# SCH_pcb-try-1_2025-03-21.net
KiCad netlist of a schematic drawn in EasyEDA
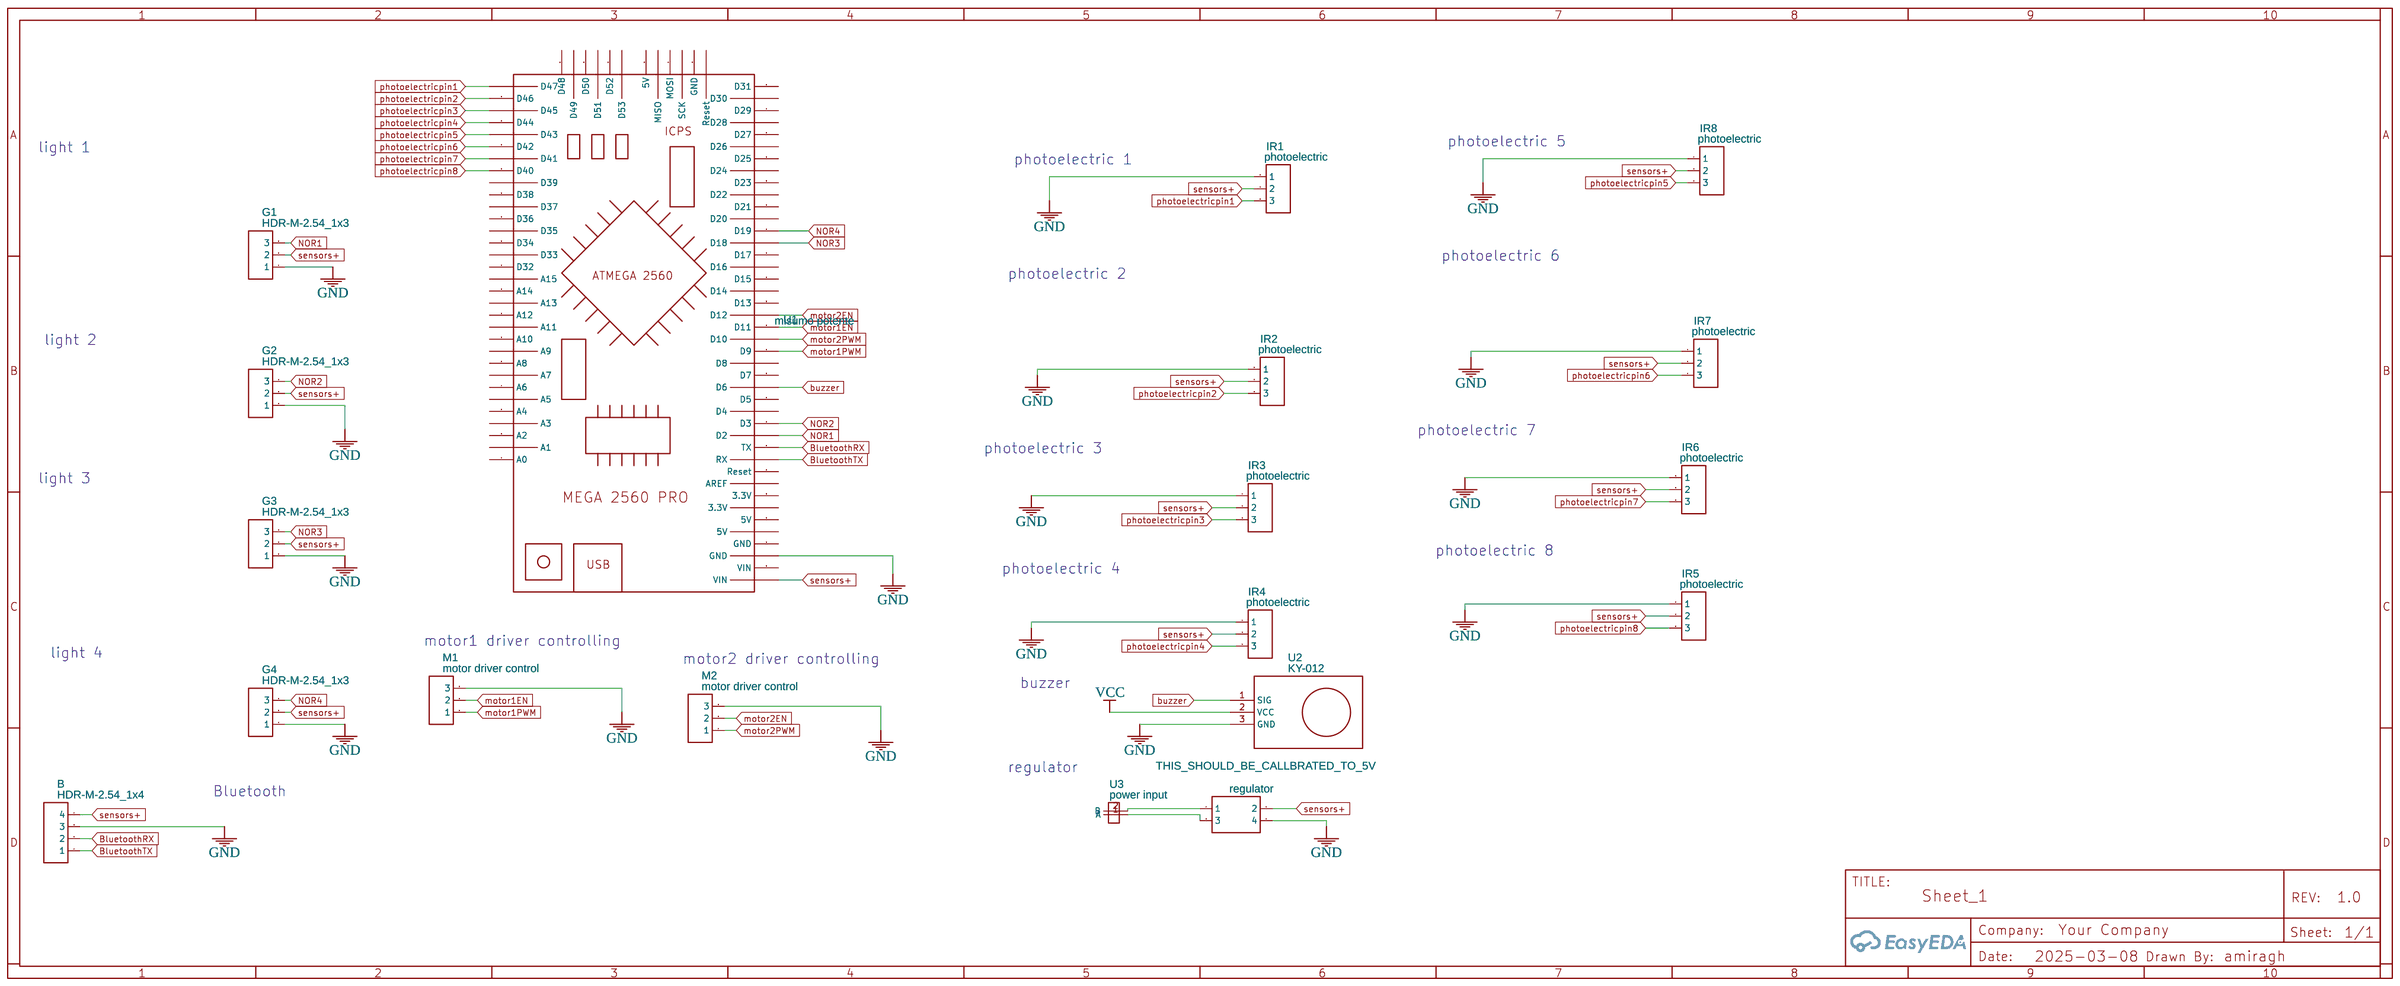
[diagram p0: schematic sheet]

(export (version "E")
  (design (tool "Eeschema 10.0.6"))
  (components
    (comp (ref "B") (value "HDR-M-2.54_1x4") (libsource (lib "") (part "HDR-M-2.54_1x4")))
    (comp (ref "G1") (value "HDR-M-2.54_1x3") (libsource (lib "") (part "HDR-M-2.54_1x3_1")))
    (comp (ref "G2") (value "HDR-M-2.54_1x3") (libsource (lib "") (part "HDR-M-2.54_1x3_1")))
    (comp (ref "G3") (value "HDR-M-2.54_1x3") (libsource (lib "") (part "HDR-M-2.54_1x3_1")))
    (comp (ref "G4") (value "HDR-M-2.54_1x3") (libsource (lib "") (part "HDR-M-2.54_1x3_1")))
    (comp (ref "IR1") (value "photoelectric") (libsource (lib "") (part "HDR-M-2.54_1x3")))
    (comp (ref "IR2") (value "photoelectric") (libsource (lib "") (part "HDR-M-2.54_1x3")))
    (comp (ref "IR3") (value "photoelectric") (libsource (lib "") (part "HDR-M-2.54_1x3")))
    (comp (ref "IR4") (value "photoelectric") (libsource (lib "") (part "HDR-M-2.54_1x3")))
    (comp (ref "IR5") (value "photoelectric") (libsource (lib "") (part "HDR-M-2.54_1x3")))
    (comp (ref "IR6") (value "photoelectric") (libsource (lib "") (part "HDR-M-2.54_1x3")))
    (comp (ref "IR7") (value "photoelectric") (libsource (lib "") (part "HDR-M-2.54_1x3")))
    (comp (ref "IR8") (value "photoelectric") (libsource (lib "") (part "HDR-M-2.54_1x3")))
    (comp (ref "M1") (value "motor driver control") (libsource (lib "") (part "HDR-M-2.54_1x3_2")))
    (comp (ref "M2") (value "motor driver control") (libsource (lib "") (part "HDR-M-2.54_1x3_2")))
    (comp (ref "THIS_SHOULD_BE_CALLBRATED_TO_5V")
      (value "regulator")
      (libsource (lib "") (part "HDR-M-2.54_2x2"))
    )
    (comp (ref "U1")
      (value "misumo potente")
      (fields (field (name "Manufacturer Part") "Arduino Mega 2560 Pro Mini"))
      (libsource (lib "") (part "misumo potente"))
    )
    (comp (ref "U2") (value "KY-012") (libsource (lib "") (part "KY-012")))
    (comp (ref "U3")
      (value "power input")
      (fields (field (name "Manufacturer Part") "1725656") (field (name "Manufacturer") "Phoenix Contact"))
      (libsource (lib "") (part "SCHLIB_2-Pin-Fixed-Terminal-Blocks-2.54-mm_2025-03-11"))
    )
  )
  (nets
    (net (code "1") (name "BluetoothRX") (class "Default")
      (node (ref "B") (pin "2") (pinfunction "2_2") (pintype "unspecified"))
      (node (ref "U1") (pin "75") (pinfunction "TX_75") (pintype "unspecified"))
    )
    (net (code "2") (name "BluetoothTX") (class "Default")
      (node (ref "B") (pin "1") (pinfunction "1_1") (pintype "unspecified"))
      (node (ref "U1") (pin "76") (pinfunction "RX_76") (pintype "unspecified"))
    )
    (net (code "3") (name "GND") (class "Default")
      (node (ref "B") (pin "3") (pinfunction "3_3") (pintype "unspecified"))
      (node (ref "G1") (pin "1") (pinfunction "1_1") (pintype "input"))
      (node (ref "G2") (pin "1") (pinfunction "1_1") (pintype "input"))
      (node (ref "G3") (pin "1") (pinfunction "1_1") (pintype "input"))
      (node (ref "G4") (pin "1") (pinfunction "1_1") (pintype "input"))
      (node (ref "IR1") (pin "1") (pinfunction "1_1") (pintype "input"))
      (node (ref "IR2") (pin "1") (pinfunction "1_1") (pintype "input"))
      (node (ref "IR3") (pin "1") (pinfunction "1_1") (pintype "input"))
      (node (ref "IR4") (pin "1") (pinfunction "1_1") (pintype "input"))
      (node (ref "IR5") (pin "1") (pinfunction "1_1") (pintype "input"))
      (node (ref "IR6") (pin "1") (pinfunction "1_1") (pintype "input"))
      (node (ref "IR7") (pin "1") (pinfunction "1_1") (pintype "input"))
      (node (ref "IR8") (pin "1") (pinfunction "1_1") (pintype "input"))
      (node (ref "M1") (pin "3") (pinfunction "3_3") (pintype "input"))
      (node (ref "M2") (pin "3") (pinfunction "3_3") (pintype "input"))
      (node (ref "THIS_SHOULD_BE_CALLBRATED_TO_5V") (pin "4") (pinfunction "4_4") (pintype "input"))
      (node (ref "U1") (pin "84") (pinfunction "GND_84") (pintype "unspecified"))
      (node (ref "U2") (pin "3") (pinfunction "GND_3") (pintype "unspecified"))
    )
    (net (code "4") (name "NOR1") (class "Default")
      (node (ref "G1") (pin "3") (pinfunction "3_3") (pintype "input"))
      (node (ref "U1") (pin "74") (pinfunction "D2_74") (pintype "unspecified"))
    )
    (net (code "5") (name "NOR2") (class "Default")
      (node (ref "G2") (pin "3") (pinfunction "3_3") (pintype "input"))
      (node (ref "U1") (pin "73") (pinfunction "D3_73") (pintype "unspecified"))
    )
    (net (code "6") (name "NOR3") (class "Default")
      (node (ref "G3") (pin "3") (pinfunction "3_3") (pintype "input"))
      (node (ref "U1") (pin "58") (pinfunction "D18_58") (pintype "unspecified"))
    )
    (net (code "7") (name "NOR4") (class "Default")
      (node (ref "G4") (pin "3") (pinfunction "3_3") (pintype "input"))
      (node (ref "U1") (pin "57") (pinfunction "D19_57") (pintype "unspecified"))
    )
    (net (code "8") (name "Net-(U3-A)") (class "Default")
      (node (ref "THIS_SHOULD_BE_CALLBRATED_TO_5V") (pin "3") (pinfunction "3_3") (pintype "input"))
      (node (ref "U3") (pin "1") (pinfunction "A_1") (pintype "unspecified"))
    )
    (net (code "9") (name "Net-(U3-B)") (class "Default")
      (node (ref "THIS_SHOULD_BE_CALLBRATED_TO_5V") (pin "1") (pinfunction "1_1") (pintype "input"))
      (node (ref "U3") (pin "2") (pinfunction "B_2") (pintype "unspecified"))
    )
    (net (code "10") (name "VCC") (class "Default")
      (node (ref "U2") (pin "2") (pinfunction "VCC_2") (pintype "unspecified"))
    )
    (net (code "11") (name "buzzer") (class "Default")
      (node (ref "U1") (pin "70") (pinfunction "D6_70") (pintype "unspecified"))
      (node (ref "U2") (pin "1") (pinfunction "SIG_1") (pintype "unspecified"))
    )
    (net (code "12") (name "motor1EN") (class "Default")
      (node (ref "M1") (pin "2") (pinfunction "2_2") (pintype "input"))
      (node (ref "U1") (pin "65") (pinfunction "D11_65") (pintype "unspecified"))
    )
    (net (code "13") (name "motor1PWM") (class "Default")
      (node (ref "M1") (pin "1") (pinfunction "1_1") (pintype "input"))
      (node (ref "U1") (pin "67") (pinfunction "D9_67") (pintype "unspecified"))
    )
    (net (code "14") (name "motor2EN") (class "Default")
      (node (ref "M2") (pin "2") (pinfunction "2_2") (pintype "input"))
      (node (ref "U1") (pin "64") (pinfunction "D12_64") (pintype "unspecified"))
    )
    (net (code "15") (name "motor2PWM") (class "Default")
      (node (ref "M2") (pin "1") (pinfunction "1_1") (pintype "input"))
      (node (ref "U1") (pin "66") (pinfunction "D10_66") (pintype "unspecified"))
    )
    (net (code "16") (name "photoelectricpin1") (class "Default")
      (node (ref "IR1") (pin "3") (pinfunction "3_3") (pintype "input"))
      (node (ref "U1") (pin "32") (pinfunction "D47_32") (pintype "unspecified"))
    )
    (net (code "17") (name "photoelectricpin2") (class "Default")
      (node (ref "IR2") (pin "3") (pinfunction "3_3") (pintype "input"))
      (node (ref "U1") (pin "31") (pinfunction "D46_31") (pintype "unspecified"))
    )
    (net (code "18") (name "photoelectricpin3") (class "Default")
      (node (ref "IR3") (pin "3") (pinfunction "3_3") (pintype "input"))
      (node (ref "U1") (pin "30") (pinfunction "D45_30") (pintype "unspecified"))
    )
    (net (code "19") (name "photoelectricpin4") (class "Default")
      (node (ref "IR4") (pin "3") (pinfunction "3_3") (pintype "input"))
      (node (ref "U1") (pin "29") (pinfunction "D44_29") (pintype "unspecified"))
    )
    (net (code "20") (name "photoelectricpin5") (class "Default")
      (node (ref "IR8") (pin "3") (pinfunction "3_3") (pintype "input"))
      (node (ref "U1") (pin "28") (pinfunction "D43_28") (pintype "unspecified"))
    )
    (net (code "21") (name "photoelectricpin6") (class "Default")
      (node (ref "IR7") (pin "3") (pinfunction "3_3") (pintype "input"))
      (node (ref "U1") (pin "27") (pinfunction "D42_27") (pintype "unspecified"))
    )
    (net (code "22") (name "photoelectricpin7") (class "Default")
      (node (ref "IR6") (pin "3") (pinfunction "3_3") (pintype "input"))
      (node (ref "U1") (pin "26") (pinfunction "D41_26") (pintype "unspecified"))
    )
    (net (code "23") (name "photoelectricpin8") (class "Default")
      (node (ref "IR5") (pin "3") (pinfunction "3_3") (pintype "input"))
      (node (ref "U1") (pin "25") (pinfunction "D40_25") (pintype "unspecified"))
    )
    (net (code "24") (name "sensors+") (class "Default")
      (node (ref "B") (pin "4") (pinfunction "4_4") (pintype "unspecified"))
      (node (ref "G1") (pin "2") (pinfunction "2_2") (pintype "input"))
      (node (ref "G2") (pin "2") (pinfunction "2_2") (pintype "input"))
      (node (ref "G3") (pin "2") (pinfunction "2_2") (pintype "input"))
      (node (ref "G4") (pin "2") (pinfunction "2_2") (pintype "input"))
      (node (ref "IR1") (pin "2") (pinfunction "2_2") (pintype "input"))
      (node (ref "IR2") (pin "2") (pinfunction "2_2") (pintype "input"))
      (node (ref "IR3") (pin "2") (pinfunction "2_2") (pintype "input"))
      (node (ref "IR4") (pin "2") (pinfunction "2_2") (pintype "input"))
      (node (ref "IR5") (pin "2") (pinfunction "2_2") (pintype "input"))
      (node (ref "IR6") (pin "2") (pinfunction "2_2") (pintype "input"))
      (node (ref "IR7") (pin "2") (pinfunction "2_2") (pintype "input"))
      (node (ref "IR8") (pin "2") (pinfunction "2_2") (pintype "input"))
      (node (ref "THIS_SHOULD_BE_CALLBRATED_TO_5V") (pin "2") (pinfunction "2_2") (pintype "input"))
      (node (ref "U1") (pin "86") (pinfunction "VIN_86") (pintype "unspecified"))
    )
    (net (code "25") (name "unconnected-(U1-3.3V-Pad79)") (class "Default")
      (node (ref "U1") (pin "79") (pinfunction "3.3V_79") (pintype "unspecified"))
    )
    (net (code "26") (name "unconnected-(U1-3.3V-Pad80)") (class "Default")
      (node (ref "U1") (pin "80") (pinfunction "3.3V_80") (pintype "unspecified"))
    )
    (net (code "27") (name "unconnected-(U1-5V-Pad39)") (class "Default")
      (node (ref "U1") (pin "39") (pinfunction "5V_39") (pintype "unspecified"))
    )
    (net (code "28") (name "unconnected-(U1-5V-Pad81)") (class "Default")
      (node (ref "U1") (pin "81") (pinfunction "5V_81") (pintype "unspecified"))
    )
    (net (code "29") (name "unconnected-(U1-5V-Pad82)") (class "Default")
      (node (ref "U1") (pin "82") (pinfunction "5V_82") (pintype "unspecified"))
    )
    (net (code "30") (name "unconnected-(U1-A0-Pad1)") (class "Default")
      (node (ref "U1") (pin "1") (pinfunction "A0_1") (pintype "unspecified"))
    )
    (net (code "31") (name "unconnected-(U1-A1-Pad2)") (class "Default")
      (node (ref "U1") (pin "2") (pinfunction "A1_2") (pintype "unspecified"))
    )
    (net (code "32") (name "unconnected-(U1-A2-Pad3)") (class "Default")
      (node (ref "U1") (pin "3") (pinfunction "A2_3") (pintype "unspecified"))
    )
    (net (code "33") (name "unconnected-(U1-A3-Pad4)") (class "Default")
      (node (ref "U1") (pin "4") (pinfunction "A3_4") (pintype "unspecified"))
    )
    (net (code "34") (name "unconnected-(U1-A4-Pad5)") (class "Default")
      (node (ref "U1") (pin "5") (pinfunction "A4_5") (pintype "unspecified"))
    )
    (net (code "35") (name "unconnected-(U1-A5-Pad6)") (class "Default")
      (node (ref "U1") (pin "6") (pinfunction "A5_6") (pintype "unspecified"))
    )
    (net (code "36") (name "unconnected-(U1-A6-Pad7)") (class "Default")
      (node (ref "U1") (pin "7") (pinfunction "A6_7") (pintype "unspecified"))
    )
    (net (code "37") (name "unconnected-(U1-A7-Pad8)") (class "Default")
      (node (ref "U1") (pin "8") (pinfunction "A7_8") (pintype "unspecified"))
    )
    (net (code "38") (name "unconnected-(U1-A8-Pad9)") (class "Default")
      (node (ref "U1") (pin "9") (pinfunction "A8_9") (pintype "unspecified"))
    )
    (net (code "39") (name "unconnected-(U1-A9-Pad10)") (class "Default")
      (node (ref "U1") (pin "10") (pinfunction "A9_10") (pintype "unspecified"))
    )
    (net (code "40") (name "unconnected-(U1-A10-Pad11)") (class "Default")
      (node (ref "U1") (pin "11") (pinfunction "A10_11") (pintype "unspecified"))
    )
    (net (code "41") (name "unconnected-(U1-A11-Pad12)") (class "Default")
      (node (ref "U1") (pin "12") (pinfunction "A11_12") (pintype "unspecified"))
    )
    (net (code "42") (name "unconnected-(U1-A12-Pad13)") (class "Default")
      (node (ref "U1") (pin "13") (pinfunction "A12_13") (pintype "unspecified"))
    )
    (net (code "43") (name "unconnected-(U1-A13-Pad14)") (class "Default")
      (node (ref "U1") (pin "14") (pinfunction "A13_14") (pintype "unspecified"))
    )
    (net (code "44") (name "unconnected-(U1-A14-Pad15)") (class "Default")
      (node (ref "U1") (pin "15") (pinfunction "A14_15") (pintype "unspecified"))
    )
    (net (code "45") (name "unconnected-(U1-A15-Pad16)") (class "Default")
      (node (ref "U1") (pin "16") (pinfunction "A15_16") (pintype "unspecified"))
    )
    (net (code "46") (name "unconnected-(U1-AREF-Pad78)") (class "Default")
      (node (ref "U1") (pin "78") (pinfunction "AREF_78") (pintype "unspecified"))
    )
    (net (code "47") (name "unconnected-(U1-D4-Pad72)") (class "Default")
      (node (ref "U1") (pin "72") (pinfunction "D4_72") (pintype "unspecified"))
    )
    (net (code "48") (name "unconnected-(U1-D5-Pad71)") (class "Default")
      (node (ref "U1") (pin "71") (pinfunction "D5_71") (pintype "unspecified"))
    )
    (net (code "49") (name "unconnected-(U1-D7-Pad69)") (class "Default")
      (node (ref "U1") (pin "69") (pinfunction "D7_69") (pintype "unspecified"))
    )
    (net (code "50") (name "unconnected-(U1-D8-Pad68)") (class "Default")
      (node (ref "U1") (pin "68") (pinfunction "D8_68") (pintype "unspecified"))
    )
    (net (code "51") (name "unconnected-(U1-D13-Pad63)") (class "Default")
      (node (ref "U1") (pin "63") (pinfunction "D13_63") (pintype "unspecified"))
    )
    (net (code "52") (name "unconnected-(U1-D14-Pad62)") (class "Default")
      (node (ref "U1") (pin "62") (pinfunction "D14_62") (pintype "unspecified"))
    )
    (net (code "53") (name "unconnected-(U1-D15-Pad61)") (class "Default")
      (node (ref "U1") (pin "61") (pinfunction "D15_61") (pintype "unspecified"))
    )
    (net (code "54") (name "unconnected-(U1-D16-Pad60)") (class "Default")
      (node (ref "U1") (pin "60") (pinfunction "D16_60") (pintype "unspecified"))
    )
    (net (code "55") (name "unconnected-(U1-D17-Pad59)") (class "Default")
      (node (ref "U1") (pin "59") (pinfunction "D17_59") (pintype "unspecified"))
    )
    (net (code "56") (name "unconnected-(U1-D20-Pad56)") (class "Default")
      (node (ref "U1") (pin "56") (pinfunction "D20_56") (pintype "unspecified"))
    )
    (net (code "57") (name "unconnected-(U1-D21-Pad55)") (class "Default")
      (node (ref "U1") (pin "55") (pinfunction "D21_55") (pintype "unspecified"))
    )
    (net (code "58") (name "unconnected-(U1-D22-Pad54)") (class "Default")
      (node (ref "U1") (pin "54") (pinfunction "D22_54") (pintype "unspecified"))
    )
    (net (code "59") (name "unconnected-(U1-D23-Pad53)") (class "Default")
      (node (ref "U1") (pin "53") (pinfunction "D23_53") (pintype "unspecified"))
    )
    (net (code "60") (name "unconnected-(U1-D24-Pad52)") (class "Default")
      (node (ref "U1") (pin "52") (pinfunction "D24_52") (pintype "unspecified"))
    )
    (net (code "61") (name "unconnected-(U1-D25-Pad51)") (class "Default")
      (node (ref "U1") (pin "51") (pinfunction "D25_51") (pintype "unspecified"))
    )
    (net (code "62") (name "unconnected-(U1-D26-Pad50)") (class "Default")
      (node (ref "U1") (pin "50") (pinfunction "D26_50") (pintype "unspecified"))
    )
    (net (code "63") (name "unconnected-(U1-D27-Pad49)") (class "Default")
      (node (ref "U1") (pin "49") (pinfunction "D27_49") (pintype "unspecified"))
    )
    (net (code "64") (name "unconnected-(U1-D28-Pad48)") (class "Default")
      (node (ref "U1") (pin "48") (pinfunction "D28_48") (pintype "unspecified"))
    )
    (net (code "65") (name "unconnected-(U1-D29-Pad47)") (class "Default")
      (node (ref "U1") (pin "47") (pinfunction "D29_47") (pintype "unspecified"))
    )
    (net (code "66") (name "unconnected-(U1-D30-Pad46)") (class "Default")
      (node (ref "U1") (pin "46") (pinfunction "D30_46") (pintype "unspecified"))
    )
    (net (code "67") (name "unconnected-(U1-D31-Pad45)") (class "Default")
      (node (ref "U1") (pin "45") (pinfunction "D31_45") (pintype "unspecified"))
    )
    (net (code "68") (name "unconnected-(U1-D32-Pad17)") (class "Default")
      (node (ref "U1") (pin "17") (pinfunction "D32_17") (pintype "unspecified"))
    )
    (net (code "69") (name "unconnected-(U1-D33-Pad18)") (class "Default")
      (node (ref "U1") (pin "18") (pinfunction "D33_18") (pintype "unspecified"))
    )
    (net (code "70") (name "unconnected-(U1-D34-Pad19)") (class "Default")
      (node (ref "U1") (pin "19") (pinfunction "D34_19") (pintype "unspecified"))
    )
    (net (code "71") (name "unconnected-(U1-D35-Pad20)") (class "Default")
      (node (ref "U1") (pin "20") (pinfunction "D35_20") (pintype "unspecified"))
    )
    (net (code "72") (name "unconnected-(U1-D36-Pad21)") (class "Default")
      (node (ref "U1") (pin "21") (pinfunction "D36_21") (pintype "unspecified"))
    )
    (net (code "73") (name "unconnected-(U1-D37-Pad22)") (class "Default")
      (node (ref "U1") (pin "22") (pinfunction "D37_22") (pintype "unspecified"))
    )
    (net (code "74") (name "unconnected-(U1-D38-Pad23)") (class "Default")
      (node (ref "U1") (pin "23") (pinfunction "D38_23") (pintype "unspecified"))
    )
    (net (code "75") (name "unconnected-(U1-D39-Pad24)") (class "Default")
      (node (ref "U1") (pin "24") (pinfunction "D39_24") (pintype "unspecified"))
    )
    (net (code "76") (name "unconnected-(U1-D48-Pad33)") (class "Default")
      (node (ref "U1") (pin "33") (pinfunction "D48_33") (pintype "unspecified"))
    )
    (net (code "77") (name "unconnected-(U1-D49-Pad34)") (class "Default")
      (node (ref "U1") (pin "34") (pinfunction "D49_34") (pintype "unspecified"))
    )
    (net (code "78") (name "unconnected-(U1-D50-Pad35)") (class "Default")
      (node (ref "U1") (pin "35") (pinfunction "D50_35") (pintype "unspecified"))
    )
    (net (code "79") (name "unconnected-(U1-D51-Pad36)") (class "Default")
      (node (ref "U1") (pin "36") (pinfunction "D51_36") (pintype "unspecified"))
    )
    (net (code "80") (name "unconnected-(U1-D52-Pad37)") (class "Default")
      (node (ref "U1") (pin "37") (pinfunction "D52_37") (pintype "unspecified"))
    )
    (net (code "81") (name "unconnected-(U1-D53-Pad38)") (class "Default")
      (node (ref "U1") (pin "38") (pinfunction "D53_38") (pintype "unspecified"))
    )
    (net (code "82") (name "unconnected-(U1-GND-Pad43)") (class "Default")
      (node (ref "U1") (pin "43") (pinfunction "GND_43") (pintype "unspecified"))
    )
    (net (code "83") (name "unconnected-(U1-GND-Pad83)") (class "Default")
      (node (ref "U1") (pin "83") (pinfunction "GND_83") (pintype "unspecified"))
    )
    (net (code "84") (name "unconnected-(U1-MISO-Pad40)") (class "Default")
      (node (ref "U1") (pin "40") (pinfunction "MISO_40") (pintype "unspecified"))
    )
    (net (code "85") (name "unconnected-(U1-MOSI-Pad41)") (class "Default")
      (node (ref "U1") (pin "41") (pinfunction "MOSI_41") (pintype "unspecified"))
    )
    (net (code "86") (name "unconnected-(U1-Reset-Pad44)") (class "Default")
      (node (ref "U1") (pin "44") (pinfunction "Reset_44") (pintype "unspecified"))
    )
    (net (code "87") (name "unconnected-(U1-Reset-Pad77)") (class "Default")
      (node (ref "U1") (pin "77") (pinfunction "Reset_77") (pintype "unspecified"))
    )
    (net (code "88") (name "unconnected-(U1-SCK-Pad42)") (class "Default")
      (node (ref "U1") (pin "42") (pinfunction "SCK_42") (pintype "unspecified"))
    )
    (net (code "89") (name "unconnected-(U1-VIN-Pad85)") (class "Default")
      (node (ref "U1") (pin "85") (pinfunction "VIN_85") (pintype "unspecified"))
    )
  )
)
